# PowerBoard_Schematic.net
KiCad netlist of a schematic drawn in Altium Designer
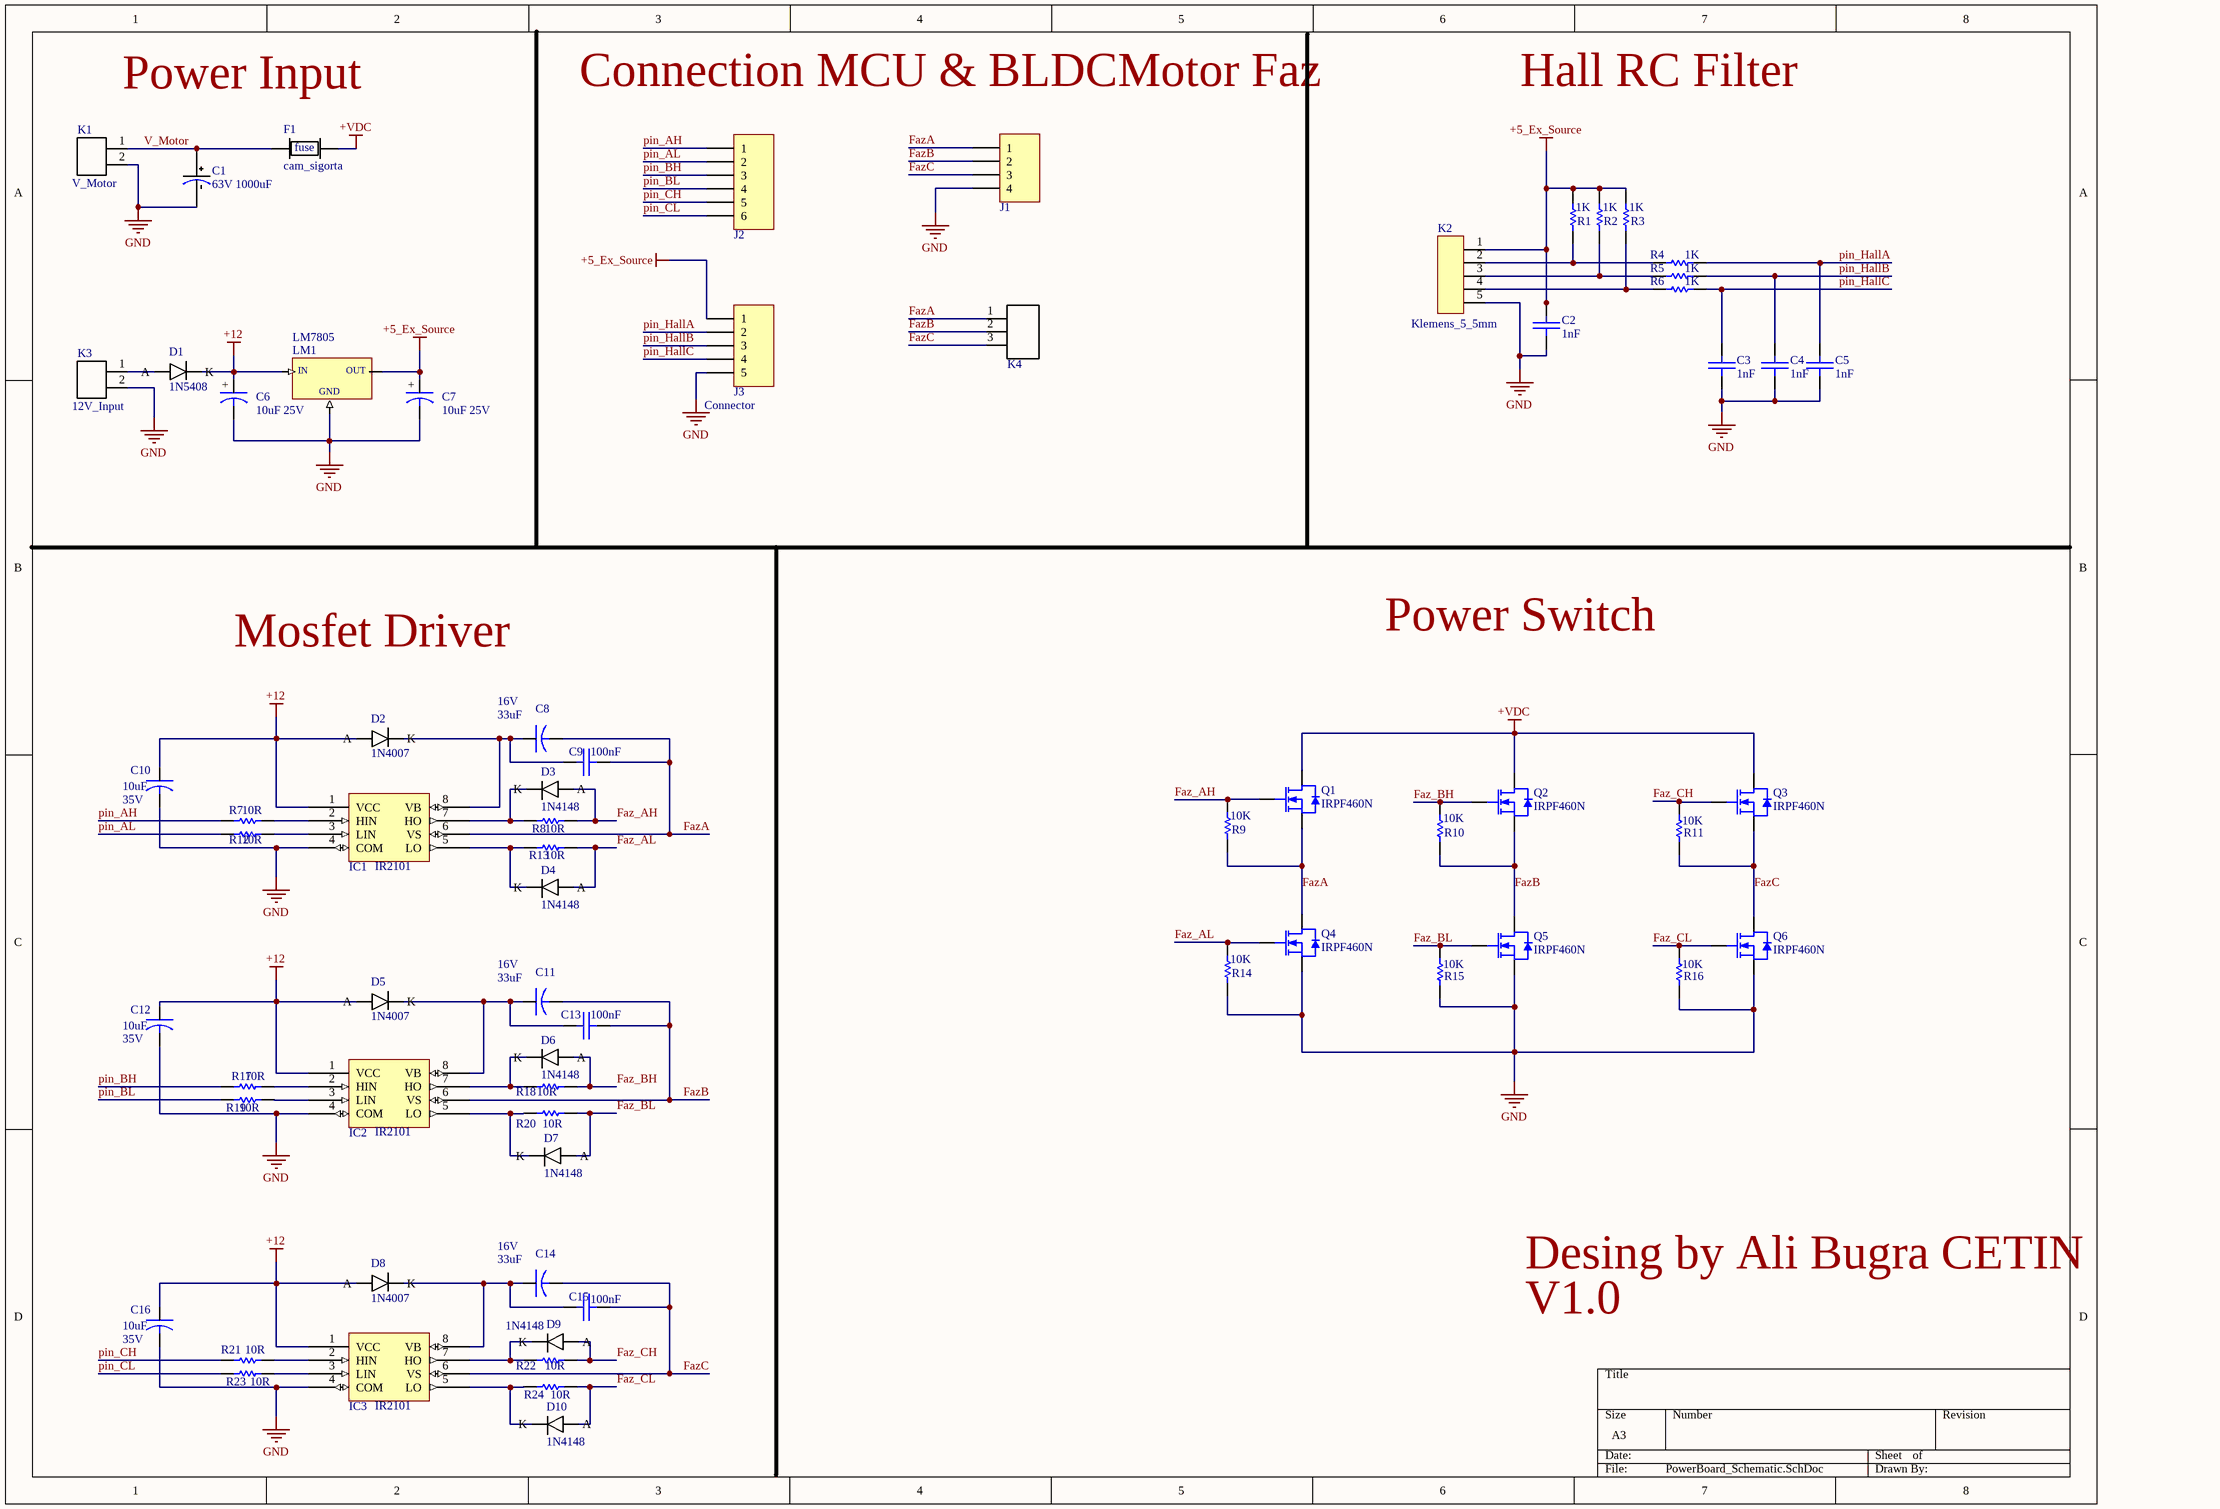
[diagram p0: PowerBoard_Schematic.SchDoc]

(export (version "E")
  (design (tool "Eeschema 10.0.6"))
  (components
    (comp (ref "C1")
      (value "63V 1000uF")
      (footprint "1000uF 10V")
      (libsource (lib "capacitors") (part "1000uF 10V"))
    )
    (comp (ref "C2") (value "1nF") (footprint "100nF") (libsource (lib "capacitors") (part "100nF")))
    (comp (ref "C3") (value "1nF") (footprint "100nF") (libsource (lib "capacitors") (part "100nF")))
    (comp (ref "C4") (value "1nF") (footprint "100nF") (libsource (lib "capacitors") (part "100nF")))
    (comp (ref "C5") (value "1nF") (footprint "100nF") (libsource (lib "capacitors") (part "100nF")))
    (comp (ref "C6")
      (value "10uF 25V")
      (footprint "10uF 35V")
      (libsource (lib "capacitors") (part "10uF 35V"))
    )
    (comp (ref "C7")
      (value "10uF 25V")
      (footprint "10uF 35V")
      (libsource (lib "capacitors") (part "10uF 35V"))
    )
    (comp (ref "C8")
      (value "33uF")
      (footprint "100uF 25v")
      (fields
        (field (name "MANUFACTURER") "Panasonic")
        (field (name "VOLTAGE") "16V")
        (field (name "Comment") "100uF 25v")
      )
      (libsource (lib "capacitors") (part "100uF 25v"))
    )
    (comp (ref "C9") (value "100nF") (footprint "100nF") (libsource (lib "capacitors") (part "100nF")))
    (comp (ref "C10")
      (value "10uF")
      (footprint "100uF 25v")
      (fields
        (field (name "MANUFACTURER") "Panasonic")
        (field (name "VOLTAGE") "35V")
        (field (name "Comment") "100uF 25v")
      )
      (libsource (lib "capacitors") (part "100uF 25v"))
    )
    (comp (ref "C11")
      (value "33uF")
      (footprint "100uF 25v")
      (fields
        (field (name "MANUFACTURER") "Panasonic")
        (field (name "VOLTAGE") "16V")
        (field (name "Comment") "100uF 25v")
      )
      (libsource (lib "capacitors") (part "100uF 25v"))
    )
    (comp (ref "C12")
      (value "10uF")
      (footprint "100uF 25v")
      (fields
        (field (name "MANUFACTURER") "Panasonic")
        (field (name "VOLTAGE") "35V")
        (field (name "Comment") "100uF 25v")
      )
      (libsource (lib "capacitors") (part "100uF 25v"))
    )
    (comp (ref "C13") (value "100nF") (footprint "100nF") (libsource (lib "capacitors") (part "100nF")))
    (comp (ref "C14")
      (value "33uF")
      (footprint "100uF 25v")
      (fields
        (field (name "MANUFACTURER") "Panasonic")
        (field (name "VOLTAGE") "16V")
        (field (name "Comment") "100uF 25v")
      )
      (libsource (lib "capacitors") (part "100uF 25v"))
    )
    (comp (ref "C15") (value "100nF") (footprint "100nF") (libsource (lib "capacitors") (part "100nF")))
    (comp (ref "C16")
      (value "10uF")
      (footprint "100uF 25v")
      (fields
        (field (name "MANUFACTURER") "Panasonic")
        (field (name "VOLTAGE") "35V")
        (field (name "Comment") "100uF 25v")
      )
      (libsource (lib "capacitors") (part "100uF 25v"))
    )
    (comp (ref "D1") (value "1N5408") (footprint "1N5408") (libsource (lib "Diode") (part "1N5408")))
    (comp (ref "D2") (value "1N4007") (footprint "1N4007") (libsource (lib "Diode") (part "1N4007")))
    (comp (ref "D3") (value "1N4148") (footprint "1N4148") (libsource (lib "Diode") (part "1N4148")))
    (comp (ref "D4") (value "1N4148") (footprint "1N4148") (libsource (lib "Diode") (part "1N4148")))
    (comp (ref "D5") (value "1N4007") (footprint "1N4007") (libsource (lib "Diode") (part "1N4007")))
    (comp (ref "D6") (value "1N4148") (footprint "1N4148") (libsource (lib "Diode") (part "1N4148")))
    (comp (ref "D7") (value "1N4148") (footprint "1N4148") (libsource (lib "Diode") (part "1N4148")))
    (comp (ref "D8") (value "1N4007") (footprint "1N4007") (libsource (lib "Diode") (part "1N4007")))
    (comp (ref "D9") (value "1N4148") (footprint "1N4148") (libsource (lib "Diode") (part "1N4148")))
    (comp (ref "D10") (value "1N4148") (footprint "1N4148") (libsource (lib "Diode") (part "1N4148")))
    (comp (ref "F1")
      (value "cam_sigorta")
      (footprint "cam_sigorta")
      (libsource (lib "Fuse") (part "cam_sigorta"))
    )
    (comp (ref "IC1") (value "IR2101") (footprint "IR2101-DIP") (libsource (lib "Entegre") (part "IR2101")))
    (comp (ref "IC2") (value "IR2101") (footprint "IR2101-DIP") (libsource (lib "Entegre") (part "IR2101")))
    (comp (ref "IC3") (value "IR2101") (footprint "IR2101-DIP") (libsource (lib "Entegre") (part "IR2101")))
    (comp (ref "J1")
      (value "Header 4x1")
      (footprint "Header 4x1")
      (libsource (lib "Header") (part "Header 4x1"))
    )
    (comp (ref "J2")
      (value "Header 6x1")
      (footprint "Header 6x1 female")
      (libsource (lib "Header") (part "Header 6x1"))
    )
    (comp (ref "J3")
      (value "Header 5x1")
      (footprint "Header 5x1 Female")
      (fields (field (name "SYSTEM") "Connector"))
      (libsource (lib "Header") (part "Header 5x1"))
    )
    (comp (ref "K1")
      (value "V_Motor")
      (footprint "Klamens_2_3.5mm")
      (libsource (lib "Header") (part "Klamens_2_3.5mm"))
    )
    (comp (ref "K2")
      (value "Klemens_5_5mm")
      (footprint "Klamens_5_5mm")
      (libsource (lib "Header") (part "Klemens_5_5mm"))
    )
    (comp (ref "K3")
      (value "12V_Input")
      (footprint "Klamens_2_3.5mm")
      (libsource (lib "Header") (part "Klamens_2_3.5mm"))
    )
    (comp (ref "K4")
      (value "Klemens_3_7.6mm")
      (footprint "Klamens_3_7.6mm")
      (libsource (lib "Header") (part "Klemens_3_7.6mm"))
    )
    (comp (ref "LM1") (value "LM7805") (footprint "LM7805") (libsource (lib "Regulator") (part "LM7805")))
    (comp (ref "Q1")
      (value "IRPF460N")
      (footprint "IRFP460N")
      (libsource (lib "Mosfet_BJT") (part "IRPF460N"))
    )
    (comp (ref "Q2") (value "IRPF460N") (footprint "IRFP460N") (libsource (lib "") (part "IRPF460N_1")))
    (comp (ref "Q3") (value "IRPF460N") (footprint "IRFP460N") (libsource (lib "") (part "IRPF460N_1")))
    (comp (ref "Q4")
      (value "IRPF460N")
      (footprint "IRFP460N")
      (libsource (lib "Mosfet_BJT") (part "IRPF460N"))
    )
    (comp (ref "Q5") (value "IRPF460N") (footprint "IRFP460N") (libsource (lib "") (part "IRPF460N_1")))
    (comp (ref "Q6") (value "IRPF460N") (footprint "IRFP460N") (libsource (lib "") (part "IRPF460N_1")))
    (comp (ref "R1") (value "1K") (footprint "RES_DIP") (libsource (lib "RES") (part "RES_DIP")))
    (comp (ref "R2") (value "1K") (footprint "RES_DIP") (libsource (lib "RES") (part "RES_DIP")))
    (comp (ref "R3") (value "1K") (footprint "RES_DIP") (libsource (lib "RES") (part "RES_DIP")))
    (comp (ref "R4") (value "1K") (footprint "RES_DIP") (libsource (lib "RES") (part "RES_DIP")))
    (comp (ref "R5") (value "1K") (footprint "RES_DIP") (libsource (lib "RES") (part "RES_DIP")))
    (comp (ref "R6") (value "1K") (footprint "RES_DIP") (libsource (lib "RES") (part "RES_DIP")))
    (comp (ref "R7") (value "10R") (footprint "RES_DIP") (libsource (lib "RES") (part "RES_DIP")))
    (comp (ref "R8") (value "10R") (footprint "RES_DIP") (libsource (lib "RES") (part "RES_DIP")))
    (comp (ref "R9") (value "10K") (footprint "RES_DIP") (libsource (lib "RES") (part "RES_DIP")))
    (comp (ref "R10") (value "10K") (footprint "RES_DIP") (libsource (lib "RES") (part "RES_DIP")))
    (comp (ref "R11") (value "10K") (footprint "RES_DIP") (libsource (lib "RES") (part "RES_DIP")))
    (comp (ref "R12") (value "10R") (footprint "RES_DIP") (libsource (lib "RES") (part "RES_DIP")))
    (comp (ref "R13") (value "10R") (footprint "RES_DIP") (libsource (lib "RES") (part "RES_DIP")))
    (comp (ref "R14") (value "10K") (footprint "RES_DIP") (libsource (lib "RES") (part "RES_DIP")))
    (comp (ref "R15") (value "10K") (footprint "RES_DIP") (libsource (lib "RES") (part "RES_DIP")))
    (comp (ref "R16") (value "10K") (footprint "RES_DIP") (libsource (lib "RES") (part "RES_DIP")))
    (comp (ref "R17") (value "10R") (footprint "RES_DIP") (libsource (lib "RES") (part "RES_DIP")))
    (comp (ref "R18") (value "10R") (footprint "RES_DIP") (libsource (lib "RES") (part "RES_DIP")))
    (comp (ref "R19") (value "10R") (footprint "RES_DIP") (libsource (lib "RES") (part "RES_DIP")))
    (comp (ref "R20") (value "10R") (footprint "RES_DIP") (libsource (lib "RES") (part "RES_DIP")))
    (comp (ref "R21") (value "10R") (footprint "RES_DIP") (libsource (lib "RES") (part "RES_DIP")))
    (comp (ref "R22") (value "10R") (footprint "RES_DIP") (libsource (lib "RES") (part "RES_DIP")))
    (comp (ref "R23") (value "10R") (footprint "RES_DIP") (libsource (lib "RES") (part "RES_DIP")))
    (comp (ref "R24") (value "10R") (footprint "RES_DIP") (libsource (lib "RES") (part "RES_DIP")))
  )
  (nets
    (net (code "1") (name "+5_Ex_Source") (class "Default")
      (node (ref "C2") (pin "1") (pinfunction "1_1") (pintype "passive"))
      (node (ref "C7") (pin "+") (pinfunction "+_+") (pintype "passive"))
      (node (ref "J3") (pin "1") (pinfunction "1_1") (pintype "passive"))
      (node (ref "K2") (pin "1") (pinfunction "1_1") (pintype "passive"))
      (node (ref "LM1") (pin "OUT") (pinfunction "OUT_OUT") (pintype "passive"))
      (node (ref "R1") (pin "2") (pinfunction "2_2") (pintype "passive"))
      (node (ref "R2") (pin "2") (pinfunction "2_2") (pintype "passive"))
      (node (ref "R3") (pin "2") (pinfunction "2_2") (pintype "passive"))
    )
    (net (code "2") (name "+12") (class "Default")
      (node (ref "C10") (pin "1") (pinfunction "1_1") (pintype "passive"))
      (node (ref "C12") (pin "1") (pinfunction "1_1") (pintype "passive"))
      (node (ref "C16") (pin "1") (pinfunction "1_1") (pintype "passive"))
      (node (ref "C6") (pin "+") (pinfunction "+_+") (pintype "passive"))
      (node (ref "D1") (pin "2") (pinfunction "K_2") (pintype "passive"))
      (node (ref "D2") (pin "1") (pinfunction "A_1") (pintype "passive"))
      (node (ref "D5") (pin "1") (pinfunction "A_1") (pintype "passive"))
      (node (ref "D8") (pin "1") (pinfunction "A_1") (pintype "passive"))
      (node (ref "IC1") (pin "1") (pinfunction "VCC_1") (pintype "power_in"))
      (node (ref "IC2") (pin "1") (pinfunction "VCC_1") (pintype "power_in"))
      (node (ref "IC3") (pin "1") (pinfunction "VCC_1") (pintype "power_in"))
      (node (ref "LM1") (pin "IN") (pinfunction "IN_IN") (pintype "input"))
    )
    (net (code "3") (name "+VDC") (class "Default")
      (node (ref "F1") (pin "2") (pinfunction "2_2") (pintype "passive"))
      (node (ref "Q1") (pin "2") (pinfunction "D_2") (pintype "passive"))
      (node (ref "Q2") (pin "2") (pinfunction "D_2") (pintype "passive"))
      (node (ref "Q3") (pin "2") (pinfunction "D_2") (pintype "passive"))
    )
    (net (code "4") (name "/FazA") (class "Default")
      (node (ref "C8") (pin "2") (pinfunction "2_2") (pintype "passive"))
      (node (ref "C9") (pin "2") (pinfunction "2_2") (pintype "passive"))
      (node (ref "IC1") (pin "6") (pinfunction "VS_6") (pintype "bidirectional"))
      (node (ref "J1") (pin "1") (pinfunction "1_1") (pintype "passive"))
      (node (ref "K4") (pin "1") (pinfunction "1_1") (pintype "passive"))
      (node (ref "Q1") (pin "3") (pinfunction "S_3") (pintype "passive"))
      (node (ref "Q4") (pin "2") (pinfunction "D_2") (pintype "passive"))
      (node (ref "R9") (pin "1") (pinfunction "1_1") (pintype "passive"))
    )
    (net (code "5") (name "/FazB") (class "Default")
      (node (ref "C11") (pin "2") (pinfunction "2_2") (pintype "passive"))
      (node (ref "C13") (pin "2") (pinfunction "2_2") (pintype "passive"))
      (node (ref "IC2") (pin "6") (pinfunction "VS_6") (pintype "bidirectional"))
      (node (ref "J1") (pin "2") (pinfunction "2_2") (pintype "passive"))
      (node (ref "K4") (pin "2") (pinfunction "2_2") (pintype "passive"))
      (node (ref "Q2") (pin "3") (pinfunction "S_3") (pintype "passive"))
      (node (ref "Q5") (pin "2") (pinfunction "D_2") (pintype "passive"))
      (node (ref "R10") (pin "1") (pinfunction "1_1") (pintype "passive"))
    )
    (net (code "6") (name "/FazC") (class "Default")
      (node (ref "C14") (pin "2") (pinfunction "2_2") (pintype "passive"))
      (node (ref "C15") (pin "2") (pinfunction "2_2") (pintype "passive"))
      (node (ref "IC3") (pin "6") (pinfunction "VS_6") (pintype "bidirectional"))
      (node (ref "J1") (pin "3") (pinfunction "3_3") (pintype "passive"))
      (node (ref "K4") (pin "3") (pinfunction "3_3") (pintype "passive"))
      (node (ref "Q3") (pin "3") (pinfunction "S_3") (pintype "passive"))
      (node (ref "Q6") (pin "2") (pinfunction "D_2") (pintype "passive"))
      (node (ref "R11") (pin "1") (pinfunction "1_1") (pintype "passive"))
    )
    (net (code "7") (name "/Faz_AH") (class "Default")
      (node (ref "D3") (pin "1") (pinfunction "A_1") (pintype "passive"))
      (node (ref "Q1") (pin "1") (pinfunction "G_1") (pintype "passive"))
      (node (ref "R8") (pin "2") (pinfunction "2_2") (pintype "passive"))
      (node (ref "R9") (pin "2") (pinfunction "2_2") (pintype "passive"))
    )
    (net (code "8") (name "/Faz_AL") (class "Default")
      (node (ref "D4") (pin "1") (pinfunction "A_1") (pintype "passive"))
      (node (ref "Q4") (pin "1") (pinfunction "G_1") (pintype "passive"))
      (node (ref "R13") (pin "2") (pinfunction "2_2") (pintype "passive"))
      (node (ref "R14") (pin "2") (pinfunction "2_2") (pintype "passive"))
    )
    (net (code "9") (name "/Faz_BH") (class "Default")
      (node (ref "D6") (pin "1") (pinfunction "A_1") (pintype "passive"))
      (node (ref "Q2") (pin "1") (pinfunction "G_1") (pintype "passive"))
      (node (ref "R10") (pin "2") (pinfunction "2_2") (pintype "passive"))
      (node (ref "R18") (pin "2") (pinfunction "2_2") (pintype "passive"))
    )
    (net (code "10") (name "/Faz_BL") (class "Default")
      (node (ref "D7") (pin "1") (pinfunction "A_1") (pintype "passive"))
      (node (ref "Q5") (pin "1") (pinfunction "G_1") (pintype "passive"))
      (node (ref "R15") (pin "2") (pinfunction "2_2") (pintype "passive"))
      (node (ref "R20") (pin "2") (pinfunction "2_2") (pintype "passive"))
    )
    (net (code "11") (name "/Faz_CH") (class "Default")
      (node (ref "D9") (pin "1") (pinfunction "A_1") (pintype "passive"))
      (node (ref "Q3") (pin "1") (pinfunction "G_1") (pintype "passive"))
      (node (ref "R11") (pin "2") (pinfunction "2_2") (pintype "passive"))
      (node (ref "R22") (pin "2") (pinfunction "2_2") (pintype "passive"))
    )
    (net (code "12") (name "/Faz_CL") (class "Default")
      (node (ref "D10") (pin "1") (pinfunction "A_1") (pintype "passive"))
      (node (ref "Q6") (pin "1") (pinfunction "G_1") (pintype "passive"))
      (node (ref "R16") (pin "2") (pinfunction "2_2") (pintype "passive"))
      (node (ref "R24") (pin "2") (pinfunction "2_2") (pintype "passive"))
    )
    (net (code "13") (name "/V_Motor") (class "Default")
      (node (ref "C1") (pin "POS") (pinfunction "POS_POS") (pintype "passive"))
      (node (ref "F1") (pin "1") (pinfunction "1_1") (pintype "passive"))
      (node (ref "K1") (pin "1") (pinfunction "1_1") (pintype "passive"))
    )
    (net (code "14") (name "/pin_AH") (class "Default")
      (node (ref "J2") (pin "1") (pinfunction "1_1") (pintype "passive"))
      (node (ref "R7") (pin "1") (pinfunction "1_1") (pintype "passive"))
    )
    (net (code "15") (name "/pin_AL") (class "Default")
      (node (ref "J2") (pin "2") (pinfunction "2_2") (pintype "passive"))
      (node (ref "R12") (pin "1") (pinfunction "1_1") (pintype "passive"))
    )
    (net (code "16") (name "/pin_BH") (class "Default")
      (node (ref "J2") (pin "3") (pinfunction "3_3") (pintype "passive"))
      (node (ref "R17") (pin "1") (pinfunction "1_1") (pintype "passive"))
    )
    (net (code "17") (name "/pin_BL") (class "Default")
      (node (ref "J2") (pin "4") (pinfunction "4_4") (pintype "passive"))
      (node (ref "R19") (pin "1") (pinfunction "1_1") (pintype "passive"))
    )
    (net (code "18") (name "/pin_CH") (class "Default")
      (node (ref "J2") (pin "5") (pinfunction "5_5") (pintype "passive"))
      (node (ref "R21") (pin "1") (pinfunction "1_1") (pintype "passive"))
    )
    (net (code "19") (name "/pin_CL") (class "Default")
      (node (ref "J2") (pin "6") (pinfunction "6_6") (pintype "passive"))
      (node (ref "R23") (pin "1") (pinfunction "1_1") (pintype "passive"))
    )
    (net (code "20") (name "/pin_HallA") (class "Default")
      (node (ref "C5") (pin "1") (pinfunction "1_1") (pintype "passive"))
      (node (ref "J3") (pin "2") (pinfunction "2_2") (pintype "passive"))
      (node (ref "R4") (pin "2") (pinfunction "2_2") (pintype "passive"))
    )
    (net (code "21") (name "/pin_HallB") (class "Default")
      (node (ref "C4") (pin "1") (pinfunction "1_1") (pintype "passive"))
      (node (ref "J3") (pin "3") (pinfunction "3_3") (pintype "passive"))
      (node (ref "R5") (pin "2") (pinfunction "2_2") (pintype "passive"))
    )
    (net (code "22") (name "/pin_HallC") (class "Default")
      (node (ref "C3") (pin "1") (pinfunction "1_1") (pintype "passive"))
      (node (ref "J3") (pin "4") (pinfunction "4_4") (pintype "passive"))
      (node (ref "R6") (pin "2") (pinfunction "2_2") (pintype "passive"))
    )
    (net (code "23") (name "GND") (class "Default")
      (node (ref "C1") (pin "NEG") (pinfunction "NEG_NEG") (pintype "passive"))
      (node (ref "C10") (pin "2") (pinfunction "2_2") (pintype "passive"))
      (node (ref "C12") (pin "2") (pinfunction "2_2") (pintype "passive"))
      (node (ref "C16") (pin "2") (pinfunction "2_2") (pintype "passive"))
      (node (ref "C2") (pin "2") (pinfunction "2_2") (pintype "passive"))
      (node (ref "C3") (pin "2") (pinfunction "2_2") (pintype "passive"))
      (node (ref "C4") (pin "2") (pinfunction "2_2") (pintype "passive"))
      (node (ref "C5") (pin "2") (pinfunction "2_2") (pintype "passive"))
      (node (ref "C6") (pin "-") (pinfunction "-_-") (pintype "passive"))
      (node (ref "C7") (pin "-") (pinfunction "-_-") (pintype "passive"))
      (node (ref "IC1") (pin "4") (pinfunction "COM_4") (pintype "bidirectional"))
      (node (ref "IC2") (pin "4") (pinfunction "COM_4") (pintype "bidirectional"))
      (node (ref "IC3") (pin "4") (pinfunction "COM_4") (pintype "bidirectional"))
      (node (ref "J1") (pin "4") (pinfunction "4_4") (pintype "passive"))
      (node (ref "J3") (pin "5") (pinfunction "5_5") (pintype "passive"))
      (node (ref "K1") (pin "2") (pinfunction "2_2") (pintype "passive"))
      (node (ref "K2") (pin "5") (pinfunction "5_5") (pintype "passive"))
      (node (ref "K3") (pin "2") (pinfunction "2_2") (pintype "passive"))
      (node (ref "LM1") (pin "GND") (pinfunction "GND_GND") (pintype "input"))
      (node (ref "Q4") (pin "3") (pinfunction "S_3") (pintype "passive"))
      (node (ref "Q5") (pin "3") (pinfunction "S_3") (pintype "passive"))
      (node (ref "Q6") (pin "3") (pinfunction "S_3") (pintype "passive"))
      (node (ref "R14") (pin "1") (pinfunction "1_1") (pintype "passive"))
      (node (ref "R15") (pin "1") (pinfunction "1_1") (pintype "passive"))
      (node (ref "R16") (pin "1") (pinfunction "1_1") (pintype "passive"))
    )
    (net (code "24") (name "Net-(D1-A)") (class "Default")
      (node (ref "D1") (pin "1") (pinfunction "A_1") (pintype "passive"))
      (node (ref "K3") (pin "1") (pinfunction "1_1") (pintype "passive"))
    )
    (net (code "25") (name "Net-(D2-K)") (class "Default")
      (node (ref "C8") (pin "1") (pinfunction "1_1") (pintype "passive"))
      (node (ref "C9") (pin "1") (pinfunction "1_1") (pintype "passive"))
      (node (ref "D2") (pin "2") (pinfunction "K_2") (pintype "passive"))
      (node (ref "IC1") (pin "8") (pinfunction "VB_8") (pintype "bidirectional"))
    )
    (net (code "26") (name "Net-(D3-K)") (class "Default")
      (node (ref "D3") (pin "2") (pinfunction "K_2") (pintype "passive"))
      (node (ref "IC1") (pin "7") (pinfunction "HO_7") (pintype "output"))
      (node (ref "R8") (pin "1") (pinfunction "1_1") (pintype "passive"))
    )
    (net (code "27") (name "Net-(D4-K)") (class "Default")
      (node (ref "D4") (pin "2") (pinfunction "K_2") (pintype "passive"))
      (node (ref "IC1") (pin "5") (pinfunction "LO_5") (pintype "output"))
      (node (ref "R13") (pin "1") (pinfunction "1_1") (pintype "passive"))
    )
    (net (code "28") (name "Net-(D5-K)") (class "Default")
      (node (ref "C11") (pin "1") (pinfunction "1_1") (pintype "passive"))
      (node (ref "C13") (pin "1") (pinfunction "1_1") (pintype "passive"))
      (node (ref "D5") (pin "2") (pinfunction "K_2") (pintype "passive"))
      (node (ref "IC2") (pin "8") (pinfunction "VB_8") (pintype "bidirectional"))
    )
    (net (code "29") (name "Net-(D6-K)") (class "Default")
      (node (ref "D6") (pin "2") (pinfunction "K_2") (pintype "passive"))
      (node (ref "IC2") (pin "7") (pinfunction "HO_7") (pintype "output"))
      (node (ref "R18") (pin "1") (pinfunction "1_1") (pintype "passive"))
    )
    (net (code "30") (name "Net-(D7-K)") (class "Default")
      (node (ref "D7") (pin "2") (pinfunction "K_2") (pintype "passive"))
      (node (ref "IC2") (pin "5") (pinfunction "LO_5") (pintype "output"))
      (node (ref "R20") (pin "1") (pinfunction "1_1") (pintype "passive"))
    )
    (net (code "31") (name "Net-(D8-K)") (class "Default")
      (node (ref "C14") (pin "1") (pinfunction "1_1") (pintype "passive"))
      (node (ref "C15") (pin "1") (pinfunction "1_1") (pintype "passive"))
      (node (ref "D8") (pin "2") (pinfunction "K_2") (pintype "passive"))
      (node (ref "IC3") (pin "8") (pinfunction "VB_8") (pintype "bidirectional"))
    )
    (net (code "32") (name "Net-(D9-K)") (class "Default")
      (node (ref "D9") (pin "2") (pinfunction "K_2") (pintype "passive"))
      (node (ref "IC3") (pin "7") (pinfunction "HO_7") (pintype "output"))
      (node (ref "R22") (pin "1") (pinfunction "1_1") (pintype "passive"))
    )
    (net (code "33") (name "Net-(D10-K)") (class "Default")
      (node (ref "D10") (pin "2") (pinfunction "K_2") (pintype "passive"))
      (node (ref "IC3") (pin "5") (pinfunction "LO_5") (pintype "output"))
      (node (ref "R24") (pin "1") (pinfunction "1_1") (pintype "passive"))
    )
    (net (code "34") (name "Net-(IC1-HIN)") (class "Default")
      (node (ref "IC1") (pin "2") (pinfunction "HIN_2") (pintype "input"))
      (node (ref "R7") (pin "2") (pinfunction "2_2") (pintype "passive"))
    )
    (net (code "35") (name "Net-(IC1-LIN)") (class "Default")
      (node (ref "IC1") (pin "3") (pinfunction "LIN_3") (pintype "input"))
      (node (ref "R12") (pin "2") (pinfunction "2_2") (pintype "passive"))
    )
    (net (code "36") (name "Net-(IC2-HIN)") (class "Default")
      (node (ref "IC2") (pin "2") (pinfunction "HIN_2") (pintype "input"))
      (node (ref "R17") (pin "2") (pinfunction "2_2") (pintype "passive"))
    )
    (net (code "37") (name "Net-(IC2-LIN)") (class "Default")
      (node (ref "IC2") (pin "3") (pinfunction "LIN_3") (pintype "input"))
      (node (ref "R19") (pin "2") (pinfunction "2_2") (pintype "passive"))
    )
    (net (code "38") (name "Net-(IC3-HIN)") (class "Default")
      (node (ref "IC3") (pin "2") (pinfunction "HIN_2") (pintype "input"))
      (node (ref "R21") (pin "2") (pinfunction "2_2") (pintype "passive"))
    )
    (net (code "39") (name "Net-(IC3-LIN)") (class "Default")
      (node (ref "IC3") (pin "3") (pinfunction "LIN_3") (pintype "input"))
      (node (ref "R23") (pin "2") (pinfunction "2_2") (pintype "passive"))
    )
    (net (code "40") (name "Net-(K2-Pad2)") (class "Default")
      (node (ref "K2") (pin "2") (pinfunction "2_2") (pintype "passive"))
      (node (ref "R1") (pin "1") (pinfunction "1_1") (pintype "passive"))
      (node (ref "R4") (pin "1") (pinfunction "1_1") (pintype "passive"))
    )
    (net (code "41") (name "Net-(K2-Pad3)") (class "Default")
      (node (ref "K2") (pin "3") (pinfunction "3_3") (pintype "passive"))
      (node (ref "R2") (pin "1") (pinfunction "1_1") (pintype "passive"))
      (node (ref "R5") (pin "1") (pinfunction "1_1") (pintype "passive"))
    )
    (net (code "42") (name "Net-(K2-Pad4)") (class "Default")
      (node (ref "K2") (pin "4") (pinfunction "4_4") (pintype "passive"))
      (node (ref "R3") (pin "1") (pinfunction "1_1") (pintype "passive"))
      (node (ref "R6") (pin "1") (pinfunction "1_1") (pintype "passive"))
    )
  )
)
